# Power_shifter.net
KiCad netlist of a schematic drawn in Altium Designer
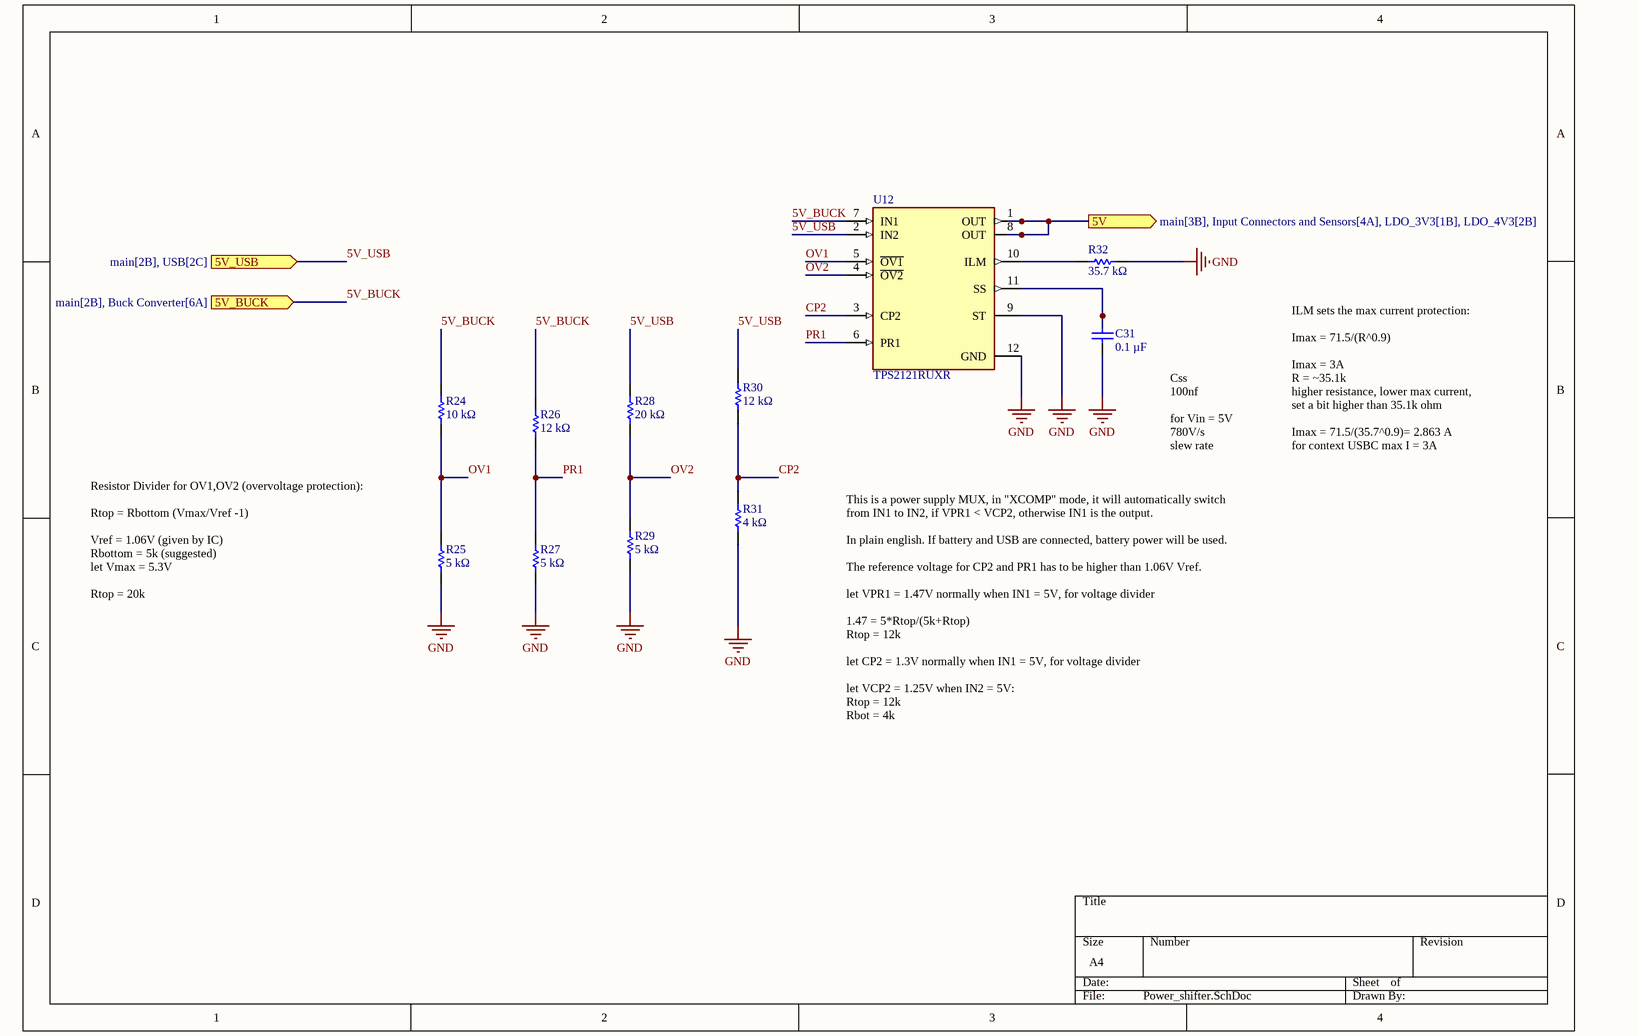
[diagram p0: Power_shifter.SchDoc]

(export (version "E")
  (design (tool "Eeschema 10.0.6"))
  (components
    (comp (ref "C31")
      (value "0.1 µF")
      (footprint "0402_CAPC1005L")
      (description "Capacitor (Semiconductor SIM Model)")
      (fields (field (name "PUBLISHER") "Altium Limited"))
      (libsource (lib "MiscDev 3") (part "Cap Semi"))
    )
    (comp (ref "R24")
      (value "10 kΩ")
      (footprint "0402_RESC1005L")
      (description "Semiconductor Resistor")
      (fields (field (name "Comment") "Res Semi") (field (name "PUBLISHER") "Altium Limited"))
      (libsource (lib "MiscDev 3") (part "Res Semi"))
    )
    (comp (ref "R25")
      (value "5 kΩ")
      (footprint "0402_RESC1005L")
      (description "Semiconductor Resistor")
      (fields (field (name "Comment") "Res Semi") (field (name "PUBLISHER") "Altium Limited"))
      (libsource (lib "MiscDev 3") (part "Res Semi"))
    )
    (comp (ref "R26")
      (value "12 kΩ")
      (footprint "0402_RESC1005L")
      (description "Semiconductor Resistor")
      (fields (field (name "Comment") "Res Semi") (field (name "PUBLISHER") "Altium Limited"))
      (libsource (lib "MiscDev 3") (part "Res Semi"))
    )
    (comp (ref "R27")
      (value "5 kΩ")
      (footprint "0402_RESC1005L")
      (description "Semiconductor Resistor")
      (fields (field (name "Comment") "Res Semi") (field (name "PUBLISHER") "Altium Limited"))
      (libsource (lib "MiscDev 3") (part "Res Semi"))
    )
    (comp (ref "R28")
      (value "20 kΩ")
      (footprint "0402_RESC1005L")
      (description "Semiconductor Resistor")
      (fields (field (name "Comment") "Res Semi") (field (name "PUBLISHER") "Altium Limited"))
      (libsource (lib "MiscDev 3") (part "Res Semi"))
    )
    (comp (ref "R29")
      (value "5 kΩ")
      (footprint "0402_RESC1005L")
      (description "Semiconductor Resistor")
      (fields (field (name "Comment") "Res Semi") (field (name "PUBLISHER") "Altium Limited"))
      (libsource (lib "MiscDev 3") (part "Res Semi"))
    )
    (comp (ref "R30")
      (value "12 kΩ")
      (footprint "0402_RESC1005L")
      (description "Semiconductor Resistor")
      (fields (field (name "Comment") "Res Semi") (field (name "PUBLISHER") "Altium Limited"))
      (libsource (lib "MiscDev 3") (part "Res Semi"))
    )
    (comp (ref "R31")
      (value "4 kΩ")
      (footprint "0402_RESC1005L")
      (description "Semiconductor Resistor")
      (fields (field (name "Comment") "Res Semi") (field (name "PUBLISHER") "Altium Limited"))
      (libsource (lib "MiscDev 3") (part "Res Semi"))
    )
    (comp (ref "R32")
      (value "35.7 kΩ")
      (footprint "0402_RESC1005L")
      (description "Semiconductor Resistor")
      (fields (field (name "Comment") "Res Semi") (field (name "PUBLISHER") "Altium Limited"))
      (libsource (lib "MiscDev 3") (part "Res Semi"))
    )
    (comp (ref "U12")
      (value "TPS2121RUXR")
      (footprint "FP-RUX0012A-MFG")
      (description "PWR MGMT BATTERY MGMT")
      (fields
        (field (name "MANUFACTURER") "Texas Instruments")
        (field (name "OCTOPART") "https://octopart.com/tps2121ruxr-texas+instruments-95511053")
      )
      (libsource (lib "Altium Content Vault") (part "7e2eec2e55e3eba557c36dfb5d176d9"))
    )
  )
  (nets
    (net (code "1") (name "/5V") (class "Default")
      (node (ref "U12") (pin "1") (pinfunction "OUT_1") (pintype "output"))
      (node (ref "U12") (pin "8") (pinfunction "OUT_8") (pintype "power_in"))
    )
    (net (code "2") (name "/5V_BUCK") (class "Default")
      (node (ref "R24") (pin "2") (pinfunction "2_2") (pintype "passive"))
      (node (ref "R26") (pin "2") (pinfunction "2_2") (pintype "passive"))
      (node (ref "U12") (pin "7") (pinfunction "IN1_7") (pintype "input"))
    )
    (net (code "3") (name "/5V_USB") (class "Default")
      (node (ref "R28") (pin "2") (pinfunction "2_2") (pintype "passive"))
      (node (ref "R30") (pin "2") (pinfunction "2_2") (pintype "passive"))
      (node (ref "U12") (pin "2") (pinfunction "IN2_2") (pintype "input"))
    )
    (net (code "4") (name "/CP2") (class "Default")
      (node (ref "R30") (pin "1") (pinfunction "1_1") (pintype "passive"))
      (node (ref "R31") (pin "2") (pinfunction "2_2") (pintype "passive"))
      (node (ref "U12") (pin "3") (pinfunction "CP2_3") (pintype "input"))
    )
    (net (code "5") (name "/OV1") (class "Default")
      (node (ref "R24") (pin "1") (pinfunction "1_1") (pintype "passive"))
      (node (ref "R25") (pin "2") (pinfunction "2_2") (pintype "passive"))
      (node (ref "U12") (pin "5") (pinfunction "~{OV1}_5") (pintype "input"))
    )
    (net (code "6") (name "/OV2") (class "Default")
      (node (ref "R28") (pin "1") (pinfunction "1_1") (pintype "passive"))
      (node (ref "R29") (pin "2") (pinfunction "2_2") (pintype "passive"))
      (node (ref "U12") (pin "4") (pinfunction "~{OV2}_4") (pintype "input"))
    )
    (net (code "7") (name "/PR1") (class "Default")
      (node (ref "R26") (pin "1") (pinfunction "1_1") (pintype "passive"))
      (node (ref "R27") (pin "2") (pinfunction "2_2") (pintype "passive"))
      (node (ref "U12") (pin "6") (pinfunction "PR1_6") (pintype "input"))
    )
    (net (code "8") (name "GND") (class "Default")
      (node (ref "C31") (pin "2") (pinfunction "2_2") (pintype "passive"))
      (node (ref "R25") (pin "1") (pinfunction "1_1") (pintype "passive"))
      (node (ref "R27") (pin "1") (pinfunction "1_1") (pintype "passive"))
      (node (ref "R29") (pin "1") (pinfunction "1_1") (pintype "passive"))
      (node (ref "R31") (pin "1") (pinfunction "1_1") (pintype "passive"))
      (node (ref "R32") (pin "1") (pinfunction "1_1") (pintype "passive"))
      (node (ref "U12") (pin "12") (pinfunction "GND_12") (pintype "power_in"))
      (node (ref "U12") (pin "9") (pinfunction "ST_9") (pintype "power_in"))
    )
    (net (code "9") (name "Net-(U12-ILM)") (class "Default")
      (node (ref "R32") (pin "2") (pinfunction "2_2") (pintype "passive"))
      (node (ref "U12") (pin "10") (pinfunction "ILM_10") (pintype "output"))
    )
    (net (code "10") (name "Net-(U12-SS)") (class "Default")
      (node (ref "C31") (pin "1") (pinfunction "1_1") (pintype "passive"))
      (node (ref "U12") (pin "11") (pinfunction "SS_11") (pintype "output"))
    )
  )
)
